# MCU.net
KiCad netlist of a schematic drawn in Altium Designer
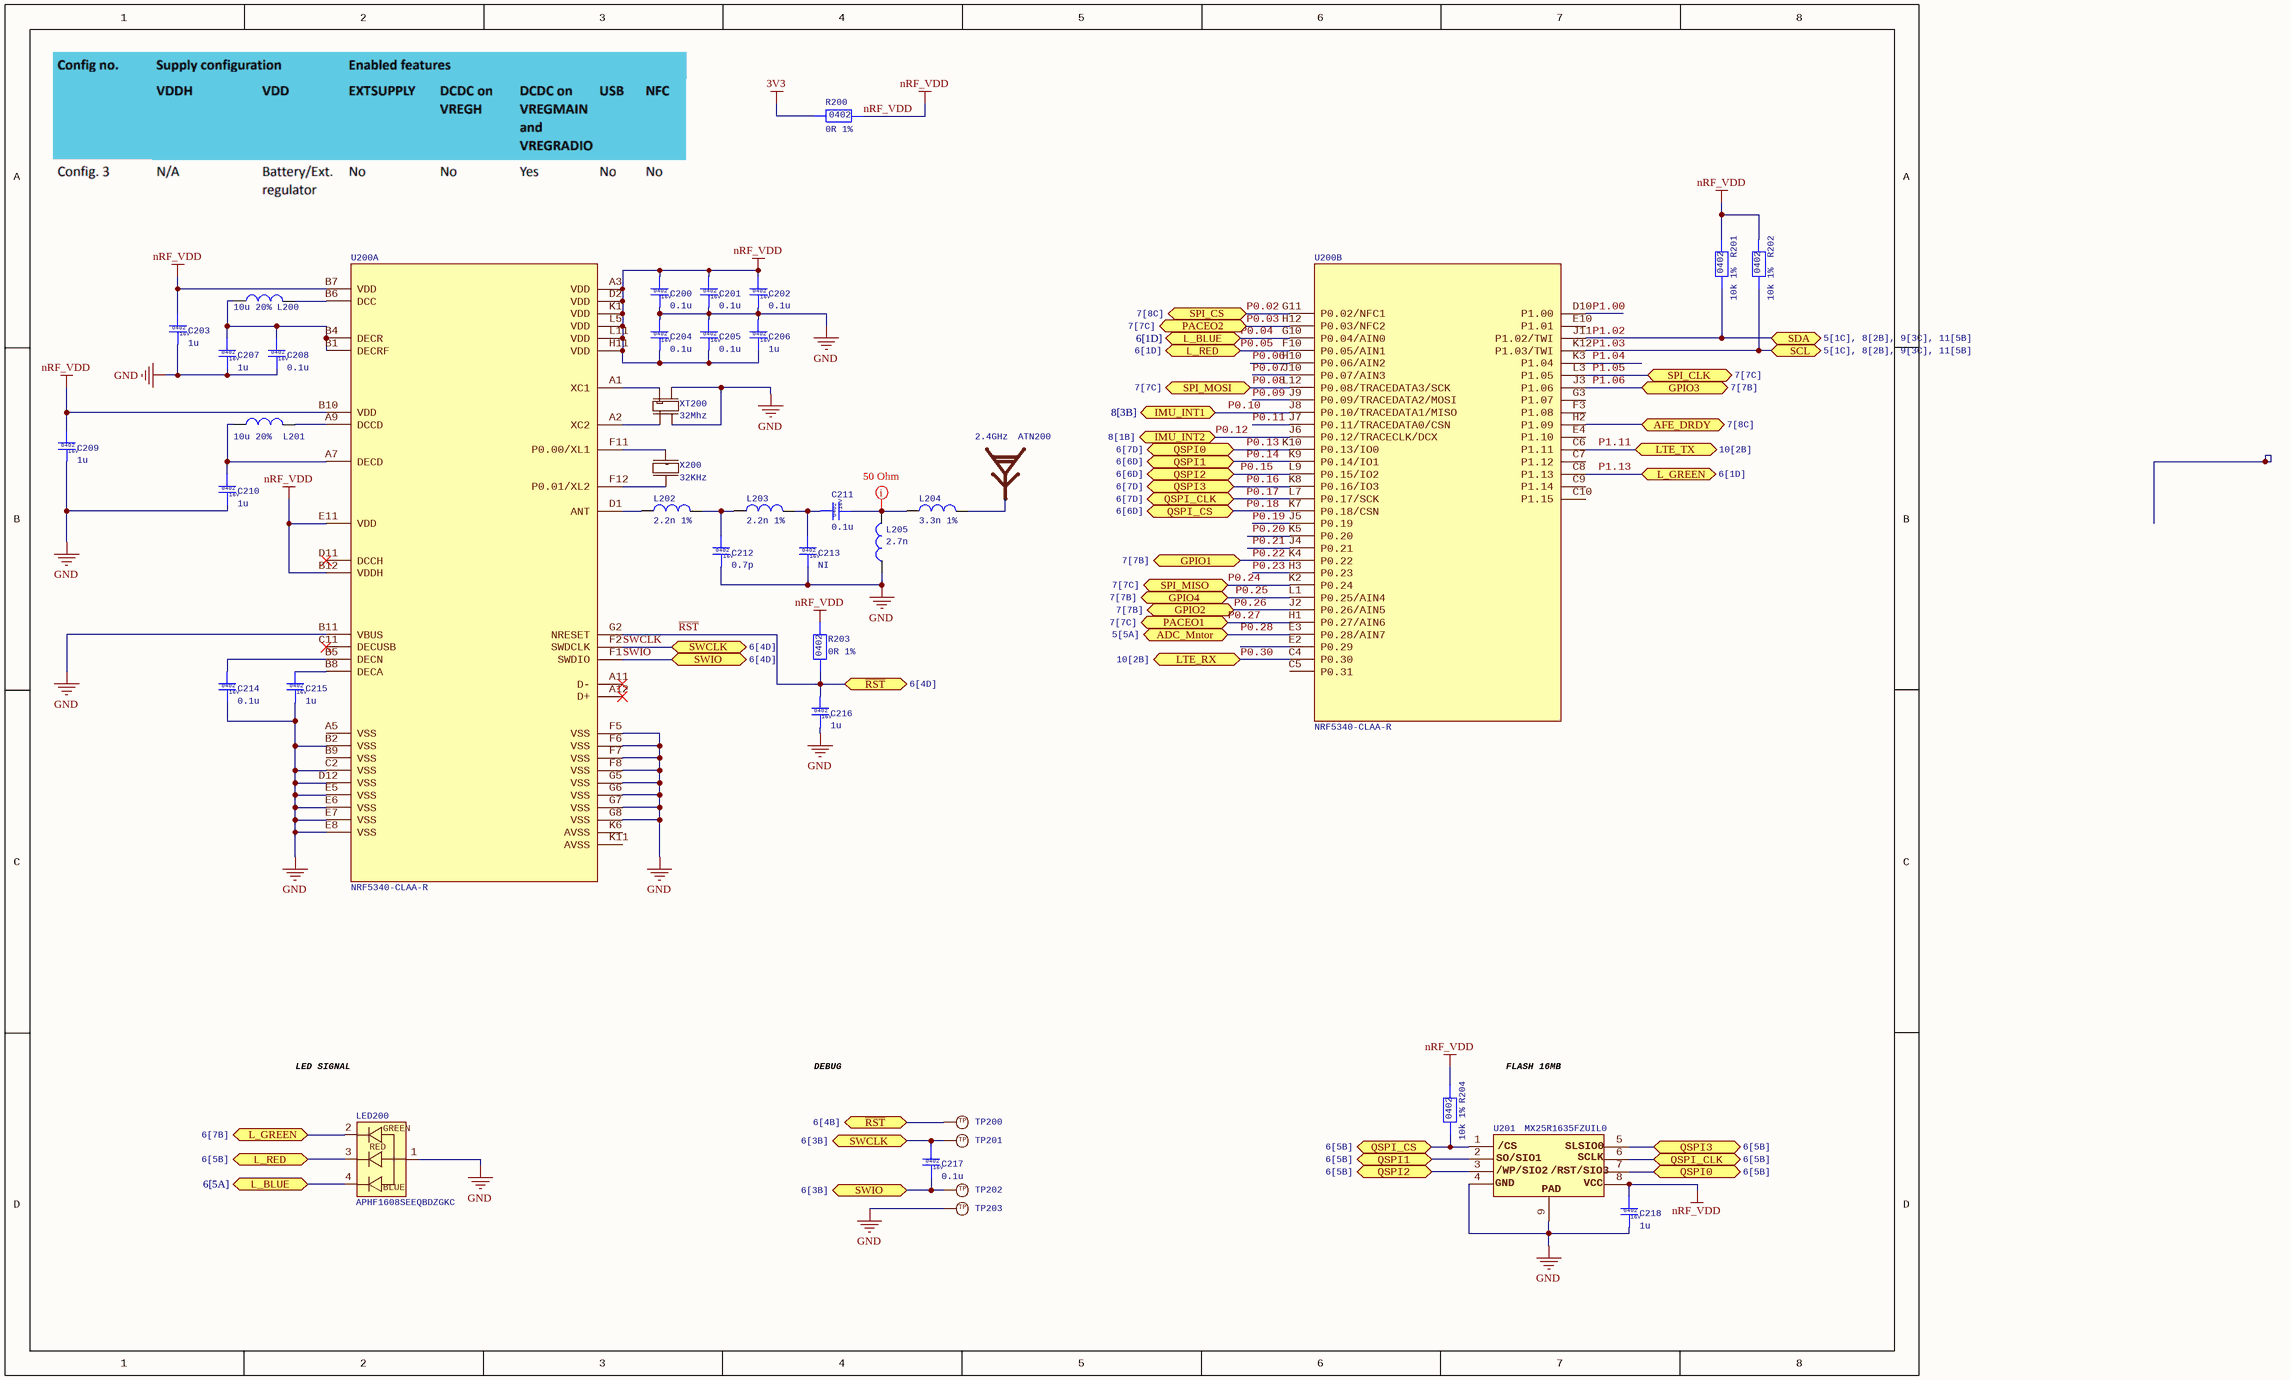
[diagram p0: MCU.SchDoc]

(export (version "E")
  (design (tool "Eeschema 10.0.6"))
  (components
    (comp (ref "ATN200")
      (value "2.4GHz")
      (footprint "2450AT18B0100001E")
      (description "Rf Ant 2.4GHZ Chip Solder SMD")
      (fields
        (field (name "MANUFACTURER") "Johanson")
        (field (name "MANUFACTURER PART NUMBER") "2450AT18B0100001E")
      )
      (libsource (lib "Hw_Lib") (part "2450AT18B0100001E"))
    )
    (comp (ref "C200")
      (value "0.1u")
      (footprint "CAP0402")
      (fields
        (field (name "MANUFACTURER") "Murata")
        (field (name "MANUFACTURER PART NUMBER") "GRM155R71C104KA88J")
      )
      (libsource (lib "Hw_Lib") (part "C_0402_0.1u"))
    )
    (comp (ref "C201")
      (value "0.1u")
      (footprint "CAP0402")
      (fields
        (field (name "MANUFACTURER") "Murata")
        (field (name "MANUFACTURER PART NUMBER") "GRM155R71C104KA88J")
      )
      (libsource (lib "Hw_Lib") (part "C_0402_0.1u"))
    )
    (comp (ref "C202")
      (value "0.1u")
      (footprint "CAP0402")
      (fields
        (field (name "MANUFACTURER") "Murata")
        (field (name "MANUFACTURER PART NUMBER") "GRM155R71C104KA88J")
      )
      (libsource (lib "Hw_Lib") (part "C_0402_0.1u"))
    )
    (comp (ref "C203")
      (value "1u")
      (footprint "CAP0402")
      (fields
        (field (name "MANUFACTURER") "Taiyo Yuden")
        (field (name "MANUFACTURER PART NUMBER") "EMK105BJ105KV-F")
      )
      (libsource (lib "Hw_Lib") (part "C_0402_1u"))
    )
    (comp (ref "C204")
      (value "0.1u")
      (footprint "CAP0402")
      (fields
        (field (name "MANUFACTURER") "Murata")
        (field (name "MANUFACTURER PART NUMBER") "GRM155R71C104KA88J")
      )
      (libsource (lib "Hw_Lib") (part "C_0402_0.1u"))
    )
    (comp (ref "C205")
      (value "0.1u")
      (footprint "CAP0402")
      (fields
        (field (name "MANUFACTURER") "Murata")
        (field (name "MANUFACTURER PART NUMBER") "GRM155R71C104KA88J")
      )
      (libsource (lib "Hw_Lib") (part "C_0402_0.1u"))
    )
    (comp (ref "C206")
      (value "1u")
      (footprint "CAP0402")
      (fields
        (field (name "MANUFACTURER") "Taiyo Yuden")
        (field (name "MANUFACTURER PART NUMBER") "EMK105BJ105KV-F")
      )
      (libsource (lib "Hw_Lib") (part "C_0402_1u"))
    )
    (comp (ref "C207")
      (value "1u")
      (footprint "CAP0402")
      (fields
        (field (name "MANUFACTURER") "Taiyo Yuden")
        (field (name "MANUFACTURER PART NUMBER") "EMK105BJ105KV-F")
      )
      (libsource (lib "Hw_Lib") (part "C_0402_1u"))
    )
    (comp (ref "C208")
      (value "0.1u")
      (footprint "CAP0402")
      (fields
        (field (name "MANUFACTURER") "Murata")
        (field (name "MANUFACTURER PART NUMBER") "GRM155R71C104KA88J")
      )
      (libsource (lib "Hw_Lib") (part "C_0402_0.1u"))
    )
    (comp (ref "C209")
      (value "1u")
      (footprint "CAP0402")
      (fields
        (field (name "MANUFACTURER") "Taiyo Yuden")
        (field (name "MANUFACTURER PART NUMBER") "EMK105BJ105KV-F")
      )
      (libsource (lib "Hw_Lib") (part "C_0402_1u"))
    )
    (comp (ref "C210")
      (value "1u")
      (footprint "CAP0402")
      (fields
        (field (name "MANUFACTURER") "Taiyo Yuden")
        (field (name "MANUFACTURER PART NUMBER") "EMK105BJ105KV-F")
      )
      (libsource (lib "Hw_Lib") (part "C_0402_1u"))
    )
    (comp (ref "C211")
      (value "0.1u")
      (footprint "CAP0402")
      (fields
        (field (name "MANUFACTURER") "Murata")
        (field (name "MANUFACTURER PART NUMBER") "GRM155R71C104KA88J")
      )
      (libsource (lib "Hw_Lib") (part "C_0402_0.1u"))
    )
    (comp (ref "C212")
      (value "0.7p")
      (footprint "CAP0402")
      (fields
        (field (name "MANUFACTURER") "Murata")
        (field (name "MANUFACTURER PART NUMBER") "GJM1555C1HR70WB01D")
      )
      (libsource (lib "Hw_Lib") (part "C_0402_0.7p"))
    )
    (comp (ref "C213")
      (value "NI")
      (footprint "CAP0402")
      (fields
        (field (name "MANUFACTURER") "Murata")
        (field (name "MANUFACTURER PART NUMBER") "GRM155R71C104KA88J")
      )
      (libsource (lib "Hw_Lib") (part "C_0402_0.1u"))
    )
    (comp (ref "C214")
      (value "0.1u")
      (footprint "CAP0402")
      (fields
        (field (name "MANUFACTURER") "Murata")
        (field (name "MANUFACTURER PART NUMBER") "GRM155R71C104KA88J")
      )
      (libsource (lib "Hw_Lib") (part "C_0402_0.1u"))
    )
    (comp (ref "C215")
      (value "1u")
      (footprint "CAP0402")
      (fields
        (field (name "MANUFACTURER") "Taiyo Yuden")
        (field (name "MANUFACTURER PART NUMBER") "EMK105BJ105KV-F")
      )
      (libsource (lib "Hw_Lib") (part "C_0402_1u"))
    )
    (comp (ref "C216")
      (value "1u")
      (footprint "CAP0402")
      (fields
        (field (name "MANUFACTURER") "Taiyo Yuden")
        (field (name "MANUFACTURER PART NUMBER") "EMK105BJ105KV-F")
      )
      (libsource (lib "Hw_Lib") (part "C_0402_1u"))
    )
    (comp (ref "C217")
      (value "0.1u")
      (footprint "CAP0402")
      (fields
        (field (name "MANUFACTURER") "Murata")
        (field (name "MANUFACTURER PART NUMBER") "GRM155R71C104KA88J")
      )
      (libsource (lib "Hw_Lib") (part "C_0402_0.1u"))
    )
    (comp (ref "C218")
      (value "1u")
      (footprint "CAP0402")
      (fields
        (field (name "MANUFACTURER") "Taiyo Yuden")
        (field (name "MANUFACTURER PART NUMBER") "EMK105BJ105KV-F")
      )
      (libsource (lib "Hw_Lib") (part "C_0402_1u"))
    )
    (comp (ref "L200")
      (value "10u 20%")
      (footprint "MLZ1608N100LTD25")
      (description "General Purpose Inductor, 10uH, 20%, 1 Element, Ferrite-Core, SMD, 0603")
      (fields
        (field (name "MANUFACTURER") "TDK")
        (field (name "MANUFACTURER PART NUMBER") "MLZ1608N100LTD25")
      )
      (libsource (lib "Hw_Lib") (part "Inductor 10u"))
    )
    (comp (ref "L201")
      (value "10u 20%")
      (footprint "MLZ1608N100LTD25")
      (description "General Purpose Inductor, 10uH, 20%, 1 Element, Ferrite-Core, SMD, 0603")
      (fields
        (field (name "MANUFACTURER") "TDK")
        (field (name "MANUFACTURER PART NUMBER") "MLZ1608N100LTD25")
      )
      (libsource (lib "Hw_Lib") (part "Inductor 10u"))
    )
    (comp (ref "L202")
      (value "2.2n 1%")
      (footprint "0402(1005) L")
      (description "General Purpose Inductor, 0.0022uH, 4.545%, 1 Element, SMD, 0402")
      (fields
        (field (name "MANUFACTURER") "Murata")
        (field (name "MANUFACTURER PART NUMBER") "LQG15HS2N2B02D")
      )
      (libsource (lib "Hw_Lib") (part "Inductor 2.2n"))
    )
    (comp (ref "L203")
      (value "2.2n 1%")
      (footprint "0402(1005) L")
      (description "General Purpose Inductor, 0.0022uH, 4.545%, 1 Element, SMD, 0402")
      (fields
        (field (name "MANUFACTURER") "Murata")
        (field (name "MANUFACTURER PART NUMBER") "LQG15HS2N2B02D")
      )
      (libsource (lib "Hw_Lib") (part "Inductor 2.2n"))
    )
    (comp (ref "L204")
      (value "3.3n 1%")
      (footprint "0402(1005) L")
      (description "General Purpose Inductor, 0.0033uH, 9.091%, 1 Element, Air-Core, SMD, 0402")
      (fields
        (field (name "MANUFACTURER") "Murata")
        (field (name "MANUFACTURER PART NUMBER") "LQG15HS3N3S02D")
      )
      (libsource (lib "Hw_Lib") (part "Inductor 3.3n"))
    )
    (comp (ref "L205")
      (value "2.7n")
      (footprint "0402(1005) L")
      (description "General Purpose Inductor, 0.0027uH, 11.111%, 1 Element, Air-Core, SMD, 0402")
      (fields
        (field (name "MANUFACTURER") "Murata")
        (field (name "MANUFACTURER PART NUMBER") "LQG15HS2N7S02D")
      )
      (libsource (lib "Hw_Lib") (part "Inductor 2.7n"))
    )
    (comp (ref "LED200")
      (value "APHF1608SEEQBDZGKC")
      (footprint "APHF1608SEEQBDZGKC")
      (description "Triple Color LED, Hyper Red/green/blue, Water Clear, 1.6mm")
      (fields (field (name "MANUFACTURER") "Kingbright"))
      (libsource (lib "Hw_Lib") (part "APHF1608SEEQBDZGKC"))
    )
    (comp (ref "R200")
      (value "0R 1%")
      (footprint "RES0402")
      (description "Metal Glaze/thick Film, 0.0625W, 0ohm, Surface Mount, 0402")
      (fields
        (field (name "MANUFACTURER") "Yageo")
        (field (name "MANUFACTURER PART NUMBER") "RC0402JR-070RL")
      )
      (libsource (lib "Hw_Lib") (part "R_0402_0R"))
    )
    (comp (ref "R201")
      (value "10k 1%")
      (footprint "R0402")
      (fields
        (field (name "MANUFACTURER") "Samsung")
        (field (name "MANUFACTURER PART NUMBER") "RC1005F103CS")
        (field (name "TOLERANCE") "1%")
      )
      (libsource (lib "Hw_Lib") (part "R_0402_10k"))
    )
    (comp (ref "R202")
      (value "10k 1%")
      (footprint "R0402")
      (fields
        (field (name "MANUFACTURER") "Samsung")
        (field (name "MANUFACTURER PART NUMBER") "RC1005F103CS")
        (field (name "TOLERANCE") "1%")
      )
      (libsource (lib "Hw_Lib") (part "R_0402_10k"))
    )
    (comp (ref "R203")
      (value "0R 1%")
      (footprint "RES0402")
      (description "Metal Glaze/thick Film, 0.0625W, 0ohm, Surface Mount, 0402")
      (fields
        (field (name "MANUFACTURER") "Yageo")
        (field (name "MANUFACTURER PART NUMBER") "RC0402JR-070RL")
      )
      (libsource (lib "Hw_Lib") (part "R_0402_0R"))
    )
    (comp (ref "R204")
      (value "10k 1%")
      (footprint "R0402")
      (fields
        (field (name "MANUFACTURER") "Samsung")
        (field (name "MANUFACTURER PART NUMBER") "RC1005F103CS")
        (field (name "TOLERANCE") "1%")
      )
      (libsource (lib "Hw_Lib") (part "R_0402_10k"))
    )
    (comp (ref "TP200")
      (value "TP")
      (footprint "TP")
      (description "Test Point")
      (libsource (lib "Hw_Lib") (part "TP"))
    )
    (comp (ref "TP201")
      (value "TP")
      (footprint "TP")
      (description "Test Point")
      (libsource (lib "Hw_Lib") (part "TP"))
    )
    (comp (ref "TP202")
      (value "TP")
      (footprint "TP")
      (description "Test Point")
      (libsource (lib "Hw_Lib") (part "TP"))
    )
    (comp (ref "TP203")
      (value "TP")
      (footprint "TP")
      (description "Test Point")
      (libsource (lib "Hw_Lib") (part "TP"))
    )
    (comp (ref "U200")
      (value "NRF5340-CLAA-R")
      (footprint "NRF5340-CLAA-R")
      (description "IC RF TXRX+MCU 802.15.4 95WLCSP")
      (fields (field (name "MANUFACTURER") "Nordic Semiconductor"))
      (libsource (lib "Hw_Lib") (part "NRF5340-CLAA-R"))
    )
    (comp (ref "U201")
      (value "MX25R1635FZUIL0")
      (footprint "MX25R1635FZUIL0")
      (description "Flash, 4MX4, PDSO8")
      (fields (field (name "MANUFACTURER") "Macronix"))
      (libsource (lib "Hw_Lib") (part "MX25R1635FZUIL0"))
    )
    (comp (ref "X200")
      (value "32KHz")
      (footprint "32Khz")
      (description "CRYSTAL 32.7680KHZ 12.5PF SMD")
      (fields
        (field (name "MANUFACTURER") "Micro Crystal")
        (field (name "MANUFACTURER PART NUMBER") "CM8V-T1A-32.768KHZ-12.5PF-20PPM-TA-QA")
      )
      (libsource (lib "Hw_Lib") (part "CM8V-T1A-32.768KHZ-12.5PF-20PPM-TA-QA"))
    )
    (comp (ref "XT200")
      (value "32Mhz")
      (footprint "XRCGB32M000F2P01R0")
      (description "Parallel - Fundamental Quartz Crystal, 32MHz Nom")
      (fields
        (field (name "MANUFACTURER") "Murata")
        (field (name "MANUFACTURER PART NUMBER") "XRCGB32M000F2P01R0")
      )
      (libsource (lib "Hw_Lib") (part "XRCGB32M000F2P01R0"))
    )
  )
  (nets
    (net (code "1") (name "/AFE_DRDY") (class "Default")
      (node (ref "U200") (pin "H2") (pinfunction "P1.09_H2") (pintype "passive"))
    )
    (net (code "2") (name "/P0.02") (class "Default")
      (node (ref "U200") (pin "G11") (pinfunction "P0.02/NFC1_G11") (pintype "passive"))
    )
    (net (code "3") (name "/P0.03") (class "Default")
      (node (ref "U200") (pin "H12") (pinfunction "P0.03/NFC2_H12") (pintype "passive"))
    )
    (net (code "4") (name "/P0.04") (class "Default")
      (node (ref "LED200") (pin "4") (pinfunction "4_4") (pintype "open_collector"))
      (node (ref "U200") (pin "G10") (pinfunction "P0.04/AIN0_G10") (pintype "passive"))
    )
    (net (code "5") (name "/P0.05") (class "Default")
      (node (ref "LED200") (pin "3") (pinfunction "3_3") (pintype "open_collector"))
      (node (ref "U200") (pin "F10") (pinfunction "P0.05/AIN1_F10") (pintype "passive"))
    )
    (net (code "6") (name "/P0.06") (class "Default")
      (node (ref "U200") (pin "H10") (pinfunction "P0.06/AIN2_H10") (pintype "passive"))
    )
    (net (code "7") (name "/P0.07") (class "Default")
      (node (ref "U200") (pin "J10") (pinfunction "P0.07/AIN3_J10") (pintype "passive"))
    )
    (net (code "8") (name "/P0.08") (class "Default")
      (node (ref "U200") (pin "L12") (pinfunction "P0.08/TRACEDATA3/SCK_L12") (pintype "passive"))
    )
    (net (code "9") (name "/P0.09") (class "Default")
      (node (ref "U200") (pin "J9") (pinfunction "P0.09/TRACEDATA2/MOSI_J9") (pintype "passive"))
    )
    (net (code "10") (name "/P0.10") (class "Default")
      (node (ref "U200") (pin "J8") (pinfunction "P0.10/TRACEDATA1/MISO_J8") (pintype "passive"))
    )
    (net (code "11") (name "/P0.11") (class "Default")
      (node (ref "U200") (pin "J7") (pinfunction "P0.11/TRACEDATA0/CSN_J7") (pintype "passive"))
    )
    (net (code "12") (name "/P0.12") (class "Default")
      (node (ref "U200") (pin "J6") (pinfunction "P0.12/TRACECLK/DCX_J6") (pintype "passive"))
    )
    (net (code "13") (name "/P0.13") (class "Default")
      (node (ref "U200") (pin "K10") (pinfunction "P0.13/IO0_K10") (pintype "passive"))
      (node (ref "U201") (pin "7") (pinfunction "7_7") (pintype "passive"))
    )
    (net (code "14") (name "/P0.14") (class "Default")
      (node (ref "U200") (pin "K9") (pinfunction "P0.14/IO1_K9") (pintype "passive"))
      (node (ref "U201") (pin "2") (pinfunction "SO/SIO1_2") (pintype "passive"))
    )
    (net (code "15") (name "/P0.15") (class "Default")
      (node (ref "U200") (pin "L9") (pinfunction "P0.15/IO2_L9") (pintype "passive"))
      (node (ref "U201") (pin "3") (pinfunction "3_3") (pintype "passive"))
    )
    (net (code "16") (name "/P0.16") (class "Default")
      (node (ref "U200") (pin "K8") (pinfunction "P0.16/IO3_K8") (pintype "passive"))
      (node (ref "U201") (pin "5") (pinfunction "5_5") (pintype "passive"))
    )
    (net (code "17") (name "/P0.17") (class "Default")
      (node (ref "U200") (pin "L7") (pinfunction "P0.17/SCK_L7") (pintype "passive"))
      (node (ref "U201") (pin "6") (pinfunction "6_6") (pintype "passive"))
    )
    (net (code "18") (name "/P0.18") (class "Default")
      (node (ref "R204") (pin "1") (pinfunction "1_1") (pintype "passive"))
      (node (ref "U200") (pin "K7") (pinfunction "P0.18/CSN_K7") (pintype "passive"))
      (node (ref "U201") (pin "1") (pinfunction "/CS_1") (pintype "passive"))
    )
    (net (code "19") (name "/P0.19") (class "Default")
      (node (ref "U200") (pin "J5") (pinfunction "P0.19_J5") (pintype "passive"))
    )
    (net (code "20") (name "/P0.20") (class "Default")
      (node (ref "U200") (pin "K5") (pinfunction "P0.20_K5") (pintype "passive"))
    )
    (net (code "21") (name "/P0.21") (class "Default")
      (node (ref "U200") (pin "J4") (pinfunction "P0.21_J4") (pintype "passive"))
    )
    (net (code "22") (name "/P0.22") (class "Default")
      (node (ref "U200") (pin "K4") (pinfunction "P0.22_K4") (pintype "passive"))
    )
    (net (code "23") (name "/P0.23") (class "Default")
      (node (ref "U200") (pin "H3") (pinfunction "P0.23_H3") (pintype "passive"))
    )
    (net (code "24") (name "/P0.24") (class "Default")
      (node (ref "U200") (pin "K2") (pinfunction "P0.24_K2") (pintype "passive"))
    )
    (net (code "25") (name "/P0.25") (class "Default")
      (node (ref "U200") (pin "L1") (pinfunction "P0.25/AIN4_L1") (pintype "passive"))
    )
    (net (code "26") (name "/P0.26") (class "Default")
      (node (ref "U200") (pin "J2") (pinfunction "P0.26/AIN5_J2") (pintype "passive"))
    )
    (net (code "27") (name "/P0.27") (class "Default")
      (node (ref "U200") (pin "H1") (pinfunction "P0.27/AIN6_H1") (pintype "passive"))
    )
    (net (code "28") (name "/P0.28") (class "Default")
      (node (ref "U200") (pin "E3") (pinfunction "P0.28/AIN7_E3") (pintype "passive"))
    )
    (net (code "29") (name "/P0.30") (class "Default")
      (node (ref "U200") (pin "C4") (pinfunction "P0.30_C4") (pintype "passive"))
    )
    (net (code "30") (name "/P1.00") (class "Default")
      (node (ref "U200") (pin "D10") (pinfunction "P1.00_D10") (pintype "passive"))
    )
    (net (code "31") (name "/P1.02") (class "Default")
      (node (ref "R201") (pin "1") (pinfunction "1_1") (pintype "passive"))
      (node (ref "U200") (pin "J11") (pinfunction "P1.02/TWI_J11") (pintype "passive"))
    )
    (net (code "32") (name "/P1.03") (class "Default")
      (node (ref "R202") (pin "1") (pinfunction "1_1") (pintype "passive"))
      (node (ref "U200") (pin "K12") (pinfunction "P1.03/TWI_K12") (pintype "passive"))
    )
    (net (code "33") (name "/P1.04") (class "Default")
      (node (ref "U200") (pin "K3") (pinfunction "P1.04_K3") (pintype "passive"))
    )
    (net (code "34") (name "/P1.05") (class "Default")
      (node (ref "U200") (pin "L3") (pinfunction "P1.05_L3") (pintype "passive"))
    )
    (net (code "35") (name "/P1.06") (class "Default")
      (node (ref "U200") (pin "J3") (pinfunction "P1.06_J3") (pintype "passive"))
    )
    (net (code "36") (name "/P1.11") (class "Default")
      (node (ref "U200") (pin "C6") (pinfunction "P1.11_C6") (pintype "passive"))
    )
    (net (code "37") (name "/P1.13") (class "Default")
      (node (ref "LED200") (pin "2") (pinfunction "2_2") (pintype "open_collector"))
      (node (ref "U200") (pin "C8") (pinfunction "P1.13_C8") (pintype "passive"))
    )
    (net (code "38") (name "/SWCLK") (class "Default")
      (node (ref "C217") (pin "1") (pinfunction "1_1") (pintype "passive"))
      (node (ref "TP201") (pin "1") (pinfunction "1_1") (pintype "passive"))
      (node (ref "U200") (pin "F2") (pinfunction "SWDCLK_F2") (pintype "passive"))
    )
    (net (code "39") (name "/SWIO") (class "Default")
      (node (ref "C217") (pin "2") (pinfunction "2_2") (pintype "passive"))
      (node (ref "TP202") (pin "1") (pinfunction "1_1") (pintype "passive"))
      (node (ref "U200") (pin "F1") (pinfunction "SWDIO_F1") (pintype "passive"))
    )
    (net (code "40") (name "/~{RST}") (class "Default")
      (node (ref "C216") (pin "1") (pinfunction "1_1") (pintype "passive"))
      (node (ref "R203") (pin "1") (pinfunction "1_1") (pintype "passive"))
      (node (ref "TP200") (pin "1") (pinfunction "1_1") (pintype "passive"))
      (node (ref "U200") (pin "G2") (pinfunction "NRESET_G2") (pintype "passive"))
    )
    (net (code "41") (name "3V3") (class "Default")
      (node (ref "R200") (pin "1") (pinfunction "1_1") (pintype "passive"))
    )
    (net (code "42") (name "GND") (class "Default")
      (node (ref "C200") (pin "2") (pinfunction "2_2") (pintype "passive"))
      (node (ref "C201") (pin "2") (pinfunction "2_2") (pintype "passive"))
      (node (ref "C202") (pin "2") (pinfunction "2_2") (pintype "passive"))
      (node (ref "C203") (pin "2") (pinfunction "2_2") (pintype "passive"))
      (node (ref "C204") (pin "1") (pinfunction "1_1") (pintype "passive"))
      (node (ref "C205") (pin "1") (pinfunction "1_1") (pintype "passive"))
      (node (ref "C206") (pin "1") (pinfunction "1_1") (pintype "passive"))
      (node (ref "C207") (pin "2") (pinfunction "2_2") (pintype "passive"))
      (node (ref "C208") (pin "2") (pinfunction "2_2") (pintype "passive"))
      (node (ref "C209") (pin "2") (pinfunction "2_2") (pintype "passive"))
      (node (ref "C210") (pin "2") (pinfunction "2_2") (pintype "passive"))
      (node (ref "C212") (pin "2") (pinfunction "2_2") (pintype "passive"))
      (node (ref "C213") (pin "2") (pinfunction "2_2") (pintype "passive"))
      (node (ref "C214") (pin "2") (pinfunction "2_2") (pintype "passive"))
      (node (ref "C215") (pin "2") (pinfunction "2_2") (pintype "passive"))
      (node (ref "C216") (pin "2") (pinfunction "2_2") (pintype "passive"))
      (node (ref "C218") (pin "2") (pinfunction "2_2") (pintype "passive"))
      (node (ref "L205") (pin "1") (pinfunction "1_1") (pintype "passive"))
      (node (ref "LED200") (pin "1") (pinfunction "1_1") (pintype "open_collector"))
      (node (ref "TP203") (pin "1") (pinfunction "1_1") (pintype "passive"))
      (node (ref "U200") (pin "B11") (pinfunction "VBUS_B11") (pintype "passive"))
      (node (ref "U200") (pin "B2") (pinfunction "VSS_B2") (pintype "passive"))
      (node (ref "U200") (pin "C2") (pinfunction "VSS_C2") (pintype "passive"))
      (node (ref "U200") (pin "D12") (pinfunction "VSS_D12") (pintype "passive"))
      (node (ref "U200") (pin "E5") (pinfunction "VSS_E5") (pintype "passive"))
      (node (ref "U200") (pin "E6") (pinfunction "VSS_E6") (pintype "passive"))
      (node (ref "U200") (pin "E7") (pinfunction "VSS_E7") (pintype "passive"))
      (node (ref "U200") (pin "E8") (pinfunction "VSS_E8") (pintype "passive"))
      (node (ref "U200") (pin "F5") (pinfunction "VSS_F5") (pintype "passive"))
      (node (ref "U200") (pin "F6") (pinfunction "VSS_F6") (pintype "passive"))
      (node (ref "U200") (pin "F7") (pinfunction "VSS_F7") (pintype "passive"))
      (node (ref "U200") (pin "F8") (pinfunction "VSS_F8") (pintype "passive"))
      (node (ref "U200") (pin "G5") (pinfunction "VSS_G5") (pintype "passive"))
      (node (ref "U200") (pin "G6") (pinfunction "VSS_G6") (pintype "passive"))
      (node (ref "U200") (pin "G7") (pinfunction "VSS_G7") (pintype "passive"))
      (node (ref "U200") (pin "G8") (pinfunction "VSS_G8") (pintype "passive"))
      (node (ref "U201") (pin "4") (pinfunction "4_4") (pintype "passive"))
      (node (ref "U201") (pin "9") (pinfunction "9_9") (pintype "passive"))
      (node (ref "XT200") (pin "2") (pinfunction "2_2") (pintype "passive"))
      (node (ref "XT200") (pin "4") (pinfunction "4_4") (pintype "passive"))
    )
    (net (code "43") (name "Net-(ATN200-Pad1)") (class "Default")
      (node (ref "ATN200") (pin "1") (pinfunction "1_1") (pintype "passive"))
      (node (ref "L204") (pin "2") (pinfunction "2_2") (pintype "passive"))
    )
    (net (code "44") (name "Net-(C211-Pad1)") (class "Default")
      (node (ref "C211") (pin "1") (pinfunction "1_1") (pintype "passive"))
      (node (ref "C213") (pin "1") (pinfunction "1_1") (pintype "passive"))
      (node (ref "L203") (pin "2") (pinfunction "2_2") (pintype "passive"))
    )
    (net (code "45") (name "Net-(C211-Pad2)") (class "Default")
      (node (ref "C211") (pin "2") (pinfunction "2_2") (pintype "passive"))
      (node (ref "L204") (pin "1") (pinfunction "1_1") (pintype "passive"))
      (node (ref "L205") (pin "2") (pinfunction "2_2") (pintype "passive"))
    )
    (net (code "46") (name "Net-(C212-Pad1)") (class "Default")
      (node (ref "C212") (pin "1") (pinfunction "1_1") (pintype "passive"))
      (node (ref "L202") (pin "2") (pinfunction "2_2") (pintype "passive"))
      (node (ref "L203") (pin "1") (pinfunction "1_1") (pintype "passive"))
    )
    (net (code "47") (name "Net-(U200A-ANT)") (class "Default")
      (node (ref "L202") (pin "1") (pinfunction "1_1") (pintype "passive"))
      (node (ref "U200") (pin "D1") (pinfunction "ANT_D1") (pintype "passive"))
    )
    (net (code "48") (name "Net-(U200A-DCC)") (class "Default")
      (node (ref "L200") (pin "2") (pinfunction "2_2") (pintype "passive"))
      (node (ref "U200") (pin "B6") (pinfunction "DCC_B6") (pintype "passive"))
    )
    (net (code "49") (name "Net-(U200A-DCCD)") (class "Default")
      (node (ref "L201") (pin "2") (pinfunction "2_2") (pintype "passive"))
      (node (ref "U200") (pin "A9") (pinfunction "DCCD_A9") (pintype "passive"))
    )
    (net (code "50") (name "Net-(U200A-DECA)") (class "Default")
      (node (ref "C215") (pin "1") (pinfunction "1_1") (pintype "passive"))
      (node (ref "U200") (pin "B8") (pinfunction "DECA_B8") (pintype "passive"))
    )
    (net (code "51") (name "Net-(U200A-DECD)") (class "Default")
      (node (ref "C210") (pin "1") (pinfunction "1_1") (pintype "passive"))
      (node (ref "L201") (pin "1") (pinfunction "1_1") (pintype "passive"))
      (node (ref "U200") (pin "A7") (pinfunction "DECD_A7") (pintype "passive"))
    )
    (net (code "52") (name "Net-(U200A-DECN)") (class "Default")
      (node (ref "C214") (pin "1") (pinfunction "1_1") (pintype "passive"))
      (node (ref "U200") (pin "B5") (pinfunction "DECN_B5") (pintype "passive"))
    )
    (net (code "53") (name "Net-(U200A-DECR)") (class "Default")
      (node (ref "C207") (pin "1") (pinfunction "1_1") (pintype "passive"))
      (node (ref "C208") (pin "1") (pinfunction "1_1") (pintype "passive"))
      (node (ref "L200") (pin "1") (pinfunction "1_1") (pintype "passive"))
      (node (ref "U200") (pin "B1") (pinfunction "DECRF_B1") (pintype "passive"))
      (node (ref "U200") (pin "B4") (pinfunction "DECR_B4") (pintype "passive"))
    )
    (net (code "54") (name "Net-(U200A-P0.00{slash}XL1)") (class "Default")
      (node (ref "U200") (pin "F11") (pinfunction "P0.00/XL1_F11") (pintype "passive"))
      (node (ref "X200") (pin "1") (pinfunction "1_1") (pintype "passive"))
    )
    (net (code "55") (name "Net-(U200A-P0.01{slash}XL2)") (class "Default")
      (node (ref "U200") (pin "F12") (pinfunction "P0.01/XL2_F12") (pintype "passive"))
      (node (ref "X200") (pin "2") (pinfunction "2_2") (pintype "passive"))
    )
    (net (code "56") (name "Net-(U200A-XC1)") (class "Default")
      (node (ref "U200") (pin "A1") (pinfunction "XC1_A1") (pintype "passive"))
      (node (ref "XT200") (pin "1") (pinfunction "1_1") (pintype "passive"))
    )
    (net (code "57") (name "Net-(U200A-XC2)") (class "Default")
      (node (ref "U200") (pin "A2") (pinfunction "XC2_A2") (pintype "passive"))
      (node (ref "XT200") (pin "3") (pinfunction "3_3") (pintype "passive"))
    )
    (net (code "58") (name "nRF_VDD") (class "Default")
      (node (ref "C200") (pin "1") (pinfunction "1_1") (pintype "passive"))
      (node (ref "C201") (pin "1") (pinfunction "1_1") (pintype "passive"))
      (node (ref "C202") (pin "1") (pinfunction "1_1") (pintype "passive"))
      (node (ref "C203") (pin "1") (pinfunction "1_1") (pintype "passive"))
      (node (ref "C204") (pin "2") (pinfunction "2_2") (pintype "passive"))
      (node (ref "C205") (pin "2") (pinfunction "2_2") (pintype "passive"))
      (node (ref "C206") (pin "2") (pinfunction "2_2") (pintype "passive"))
      (node (ref "C209") (pin "1") (pinfunction "1_1") (pintype "passive"))
      (node (ref "C218") (pin "1") (pinfunction "1_1") (pintype "passive"))
      (node (ref "R200") (pin "2") (pinfunction "2_2") (pintype "passive"))
      (node (ref "R201") (pin "2") (pinfunction "2_2") (pintype "passive"))
      (node (ref "R202") (pin "2") (pinfunction "2_2") (pintype "passive"))
      (node (ref "R203") (pin "2") (pinfunction "2_2") (pintype "passive"))
      (node (ref "R204") (pin "2") (pinfunction "2_2") (pintype "passive"))
      (node (ref "U200") (pin "A3") (pinfunction "VDD_A3") (pintype "passive"))
      (node (ref "U200") (pin "B10") (pinfunction "VDD_B10") (pintype "passive"))
      (node (ref "U200") (pin "B12") (pinfunction "VDDH_B12") (pintype "passive"))
      (node (ref "U200") (pin "B7") (pinfunction "VDD_B7") (pintype "passive"))
      (node (ref "U200") (pin "D2") (pinfunction "VDD_D2") (pintype "passive"))
      (node (ref "U200") (pin "E11") (pinfunction "VDD_E11") (pintype "passive"))
      (node (ref "U200") (pin "H11") (pinfunction "VDD_H11") (pintype "passive"))
      (node (ref "U200") (pin "K1") (pinfunction "VDD_K1") (pintype "passive"))
      (node (ref "U200") (pin "L11") (pinfunction "VDD_L11") (pintype "passive"))
      (node (ref "U200") (pin "L5") (pinfunction "VDD_L5") (pintype "passive"))
      (node (ref "U201") (pin "8") (pinfunction "8_8") (pintype "passive"))
    )
    (net (code "59") (name "unconnected-(U200A-AVSS-PadK6)") (class "Default")
      (node (ref "U200") (pin "K6") (pinfunction "AVSS_K6") (pintype "passive"))
    )
    (net (code "60") (name "unconnected-(U200A-AVSS-PadK11)") (class "Default")
      (node (ref "U200") (pin "K11") (pinfunction "AVSS_K11") (pintype "passive"))
    )
    (net (code "61") (name "unconnected-(U200A-D+-PadA12)") (class "Default")
      (node (ref "U200") (pin "A12") (pinfunction "D+_A12") (pintype "passive+no_connect"))
    )
    (net (code "62") (name "unconnected-(U200A-D--PadA11)") (class "Default")
      (node (ref "U200") (pin "A11") (pinfunction "D-_A11") (pintype "passive+no_connect"))
    )
    (net (code "63") (name "unconnected-(U200A-DCCH-PadD11)") (class "Default")
      (node (ref "U200") (pin "D11") (pinfunction "DCCH_D11") (pintype "passive+no_connect"))
    )
    (net (code "64") (name "unconnected-(U200A-DECUSB-PadC11)") (class "Default")
      (node (ref "U200") (pin "C11") (pinfunction "DECUSB_C11") (pintype "passive+no_connect"))
    )
    (net (code "65") (name "unconnected-(U200A-VSS-PadA5)") (class "Default")
      (node (ref "U200") (pin "A5") (pinfunction "VSS_A5") (pintype "passive"))
    )
    (net (code "66") (name "unconnected-(U200A-VSS-PadB9)") (class "Default")
      (node (ref "U200") (pin "B9") (pinfunction "VSS_B9") (pintype "passive"))
    )
    (net (code "67") (name "unconnected-(U200B-P0.29-PadE2)") (class "Default")
      (node (ref "U200") (pin "E2") (pinfunction "P0.29_E2") (pintype "passive"))
    )
    (net (code "68") (name "unconnected-(U200B-P0.31-PadC5)") (class "Default")
      (node (ref "U200") (pin "C5") (pinfunction "P0.31_C5") (pintype "passive"))
    )
    (net (code "69") (name "unconnected-(U200B-P1.01-PadE10)") (class "Default")
      (node (ref "U200") (pin "E10") (pinfunction "P1.01_E10") (pintype "passive"))
    )
    (net (code "70") (name "unconnected-(U200B-P1.07-PadG3)") (class "Default")
      (node (ref "U200") (pin "G3") (pinfunction "P1.07_G3") (pintype "passive"))
    )
    (net (code "71") (name "unconnected-(U200B-P1.08-PadF3)") (class "Default")
      (node (ref "U200") (pin "F3") (pinfunction "P1.08_F3") (pintype "passive"))
    )
    (net (code "72") (name "unconnected-(U200B-P1.10-PadE4)") (class "Default")
      (node (ref "U200") (pin "E4") (pinfunction "P1.10_E4") (pintype "passive"))
    )
    (net (code "73") (name "unconnected-(U200B-P1.12-PadC7)") (class "Default")
      (node (ref "U200") (pin "C7") (pinfunction "P1.12_C7") (pintype "passive"))
    )
    (net (code "74") (name "unconnected-(U200B-P1.14-PadC9)") (class "Default")
      (node (ref "U200") (pin "C9") (pinfunction "P1.14_C9") (pintype "passive"))
    )
    (net (code "75") (name "unconnected-(U200B-P1.15-PadC10)") (class "Default")
      (node (ref "U200") (pin "C10") (pinfunction "P1.15_C10") (pintype "passive"))
    )
  )
)
